# mod_mains_presence.net
KiCad netlist of a schematic drawn in EAGLE
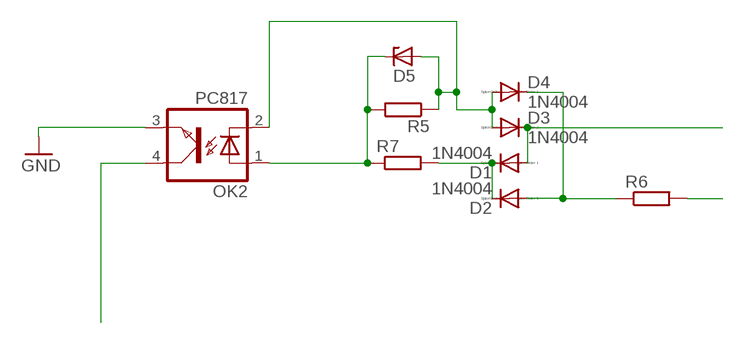
[diagram p0: schematic, sheet 1]

(export (version "E")
  (design (tool "Eeschema 10.0.6"))
  (components
    (comp (ref "D1")
      (value "1N4004")
      (footprint "eagle-import:DO41-10")
      (libsource (lib "eagle-import") (part "1N4004"))
    )
    (comp (ref "D2")
      (value "1N4004")
      (footprint "eagle-import:DO41-10")
      (libsource (lib "eagle-import") (part "1N4004"))
    )
    (comp (ref "D3")
      (value "1N4004")
      (footprint "eagle-import:DO41-10")
      (libsource (lib "eagle-import") (part "1N4004"))
    )
    (comp (ref "D4")
      (value "1N4004")
      (footprint "eagle-import:DO41-10")
      (libsource (lib "eagle-import") (part "1N4004"))
    )
    (comp (ref "D5")
      (value "ZENER-DIODEDO34-7")
      (footprint "eagle-import:DO34Z7")
      (libsource (lib "eagle-import") (part "ZENER-DIODEDO34-7"))
    )
    (comp (ref "OK2")
      (value "PC817")
      (footprint "eagle-import:DIL04")
      (fields (field (name "MPN") "PC817X4J000F"))
      (libsource (lib "eagle-import") (part "PC817"))
    )
    (comp (ref "R5")
      (value "R-EU_0204/5")
      (footprint "eagle-import:0204_5")
      (libsource (lib "eagle-import") (part "R-EU_0204/5"))
    )
    (comp (ref "R6")
      (value "R-EU_0204/7")
      (footprint "eagle-import:0204_7")
      (libsource (lib "eagle-import") (part "R-EU_0204/7"))
    )
    (comp (ref "R7")
      (value "R-EU_0204/7")
      (footprint "eagle-import:0204_7")
      (libsource (lib "eagle-import") (part "R-EU_0204/7"))
    )
  )
  (nets
    (net (code "1") (name "GND") (class "Default")
      (node (ref "OK2") (pin "3") (pinfunction "EMIT_3") (pintype "passive"))
    )
    (net (code "2") (name "Net-(D1-PadA)") (class "Default")
      (node (ref "D1") (pin "A") (pinfunction "A_A") (pintype "passive"))
      (node (ref "D3") (pin "C") (pinfunction "C_C") (pintype "passive"))
    )
    (net (code "3") (name "Net-(D1-PadC)") (class "Default")
      (node (ref "D1") (pin "C") (pinfunction "C_C") (pintype "passive"))
      (node (ref "D2") (pin "C") (pinfunction "C_C") (pintype "passive"))
      (node (ref "R7") (pin "2") (pinfunction "2_2") (pintype "passive"))
    )
    (net (code "4") (name "Net-(D2-PadA)") (class "Default")
      (node (ref "D2") (pin "A") (pinfunction "A_A") (pintype "passive"))
      (node (ref "D4") (pin "C") (pinfunction "C_C") (pintype "passive"))
      (node (ref "R6") (pin "1") (pinfunction "1_1") (pintype "passive"))
    )
    (net (code "5") (name "Net-(OK2-A)") (class "Default")
      (node (ref "D5") (pin "C") (pinfunction "C_C") (pintype "passive"))
      (node (ref "OK2") (pin "1") (pinfunction "A_1") (pintype "passive"))
      (node (ref "R5") (pin "2") (pinfunction "2_2") (pintype "passive"))
      (node (ref "R7") (pin "1") (pinfunction "1_1") (pintype "passive"))
    )
    (net (code "6") (name "Net-(OK2-C)") (class "Default")
      (node (ref "D3") (pin "A") (pinfunction "A_A") (pintype "passive"))
      (node (ref "D4") (pin "A") (pinfunction "A_A") (pintype "passive"))
      (node (ref "D5") (pin "A") (pinfunction "A_A") (pintype "passive"))
      (node (ref "OK2") (pin "2") (pinfunction "C_2") (pintype "passive"))
      (node (ref "R5") (pin "1") (pinfunction "1_1") (pintype "passive"))
    )
    (net (code "7") (name "unconnected-(OK2-COL-Pad4)") (class "Default")
      (node (ref "OK2") (pin "4") (pinfunction "COL_4") (pintype "passive"))
    )
    (net (code "8") (name "unconnected-(R6-Pad2)") (class "Default")
      (node (ref "R6") (pin "2") (pinfunction "2_2") (pintype "passive"))
    )
  )
)
